# SensePair.net
KiCad netlist of a schematic drawn in Altium Designer
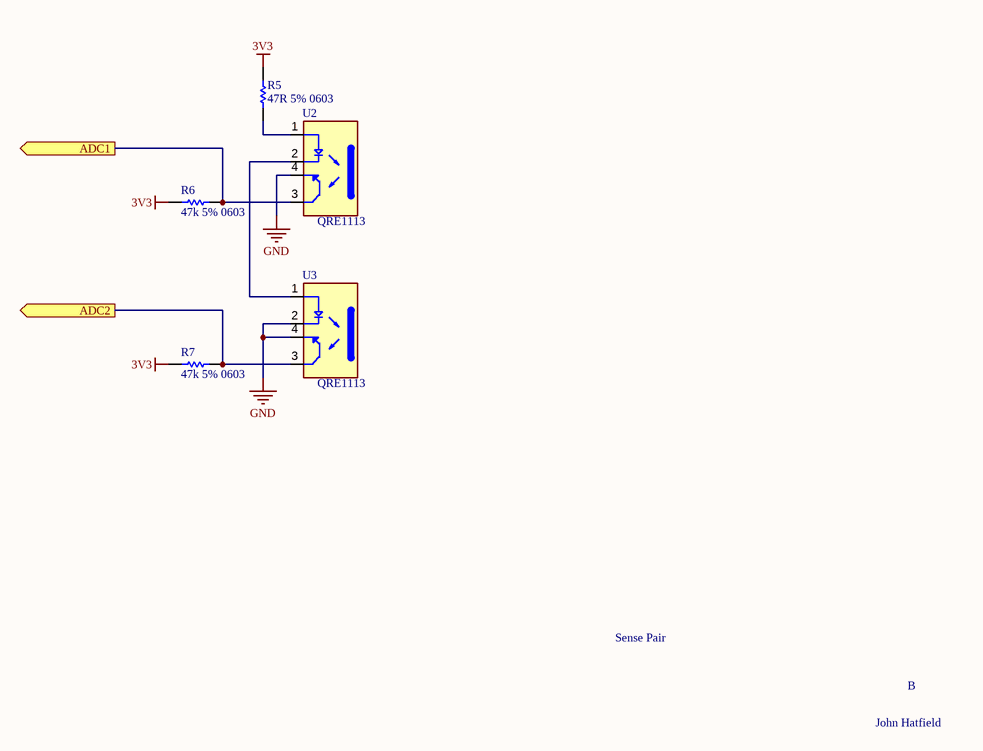
[diagram p0: SensePair.SchDoc]

(export (version "E")
  (design (tool "Eeschema 10.0.6"))
  (components
    (comp (ref "R5")
      (value "47R 5% 0603")
      (footprint "Res_ThinFilm_0603")
      (description "Resistor, SMD, 47R, 0.1W, 5%, 0603")
      (libsource (lib "StandardResistors") (part "47R 5% 0603"))
    )
    (comp (ref "R6")
      (value "47k 5% 0603")
      (footprint "Res_ThinFilm_0603")
      (description "Resistor, SMD, 47k, 0.1W, 5%, 0603")
      (libsource (lib "StandardResistors") (part "47k 5% 0603"))
    )
    (comp (ref "R7")
      (value "47k 5% 0603")
      (footprint "Res_ThinFilm_0603")
      (description "Resistor, SMD, 47k, 0.1W, 5%, 0603")
      (libsource (lib "StandardResistors") (part "47k 5% 0603"))
    )
    (comp (ref "U2")
      (value "QRE1113")
      (footprint "DIP400W50P180L360H200Q4")
      (description "Reflective Optical Sensor 0.197 _5mm_ 4-DIP _0.157, 4.00mm_")
      (fields (field (name "MF") "ON Semiconductor"))
      (libsource (lib "QRE1113") (part "QRE1113"))
    )
    (comp (ref "U3")
      (value "QRE1113")
      (footprint "DIP400W50P180L360H200Q4")
      (description "Reflective Optical Sensor 0.197 _5mm_ 4-DIP _0.157, 4.00mm_")
      (fields (field (name "MF") "ON Semiconductor"))
      (libsource (lib "QRE1113") (part "QRE1113"))
    )
  )
  (nets
    (net (code "1") (name "/ADC1") (class "Default")
      (node (ref "R6") (pin "2") (pinfunction "2_2") (pintype "passive"))
      (node (ref "U2") (pin "3") (pinfunction "CT_3") (pintype "passive"))
    )
    (net (code "2") (name "/ADC2") (class "Default")
      (node (ref "R7") (pin "2") (pinfunction "2_2") (pintype "passive"))
      (node (ref "U3") (pin "3") (pinfunction "CT_3") (pintype "passive"))
    )
    (net (code "3") (name "3V3") (class "Default")
      (node (ref "R5") (pin "2") (pinfunction "2_2") (pintype "passive"))
      (node (ref "R6") (pin "1") (pinfunction "1_1") (pintype "passive"))
      (node (ref "R7") (pin "1") (pinfunction "1_1") (pintype "passive"))
    )
    (net (code "4") (name "GND") (class "Default")
      (node (ref "U2") (pin "4") (pinfunction "ET_4") (pintype "passive"))
      (node (ref "U3") (pin "2") (pinfunction "C_2") (pintype "passive"))
      (node (ref "U3") (pin "4") (pinfunction "ET_4") (pintype "passive"))
    )
    (net (code "5") (name "Net-(U2-A)") (class "Default")
      (node (ref "R5") (pin "1") (pinfunction "1_1") (pintype "passive"))
      (node (ref "U2") (pin "1") (pinfunction "A_1") (pintype "passive"))
    )
    (net (code "6") (name "Net-(U2-C)") (class "Default")
      (node (ref "U2") (pin "2") (pinfunction "C_2") (pintype "passive"))
      (node (ref "U3") (pin "1") (pinfunction "A_1") (pintype "passive"))
    )
  )
)
